# UCirKitUserStudy4-2.net
KiCad netlist of a schematic drawn in EAGLE
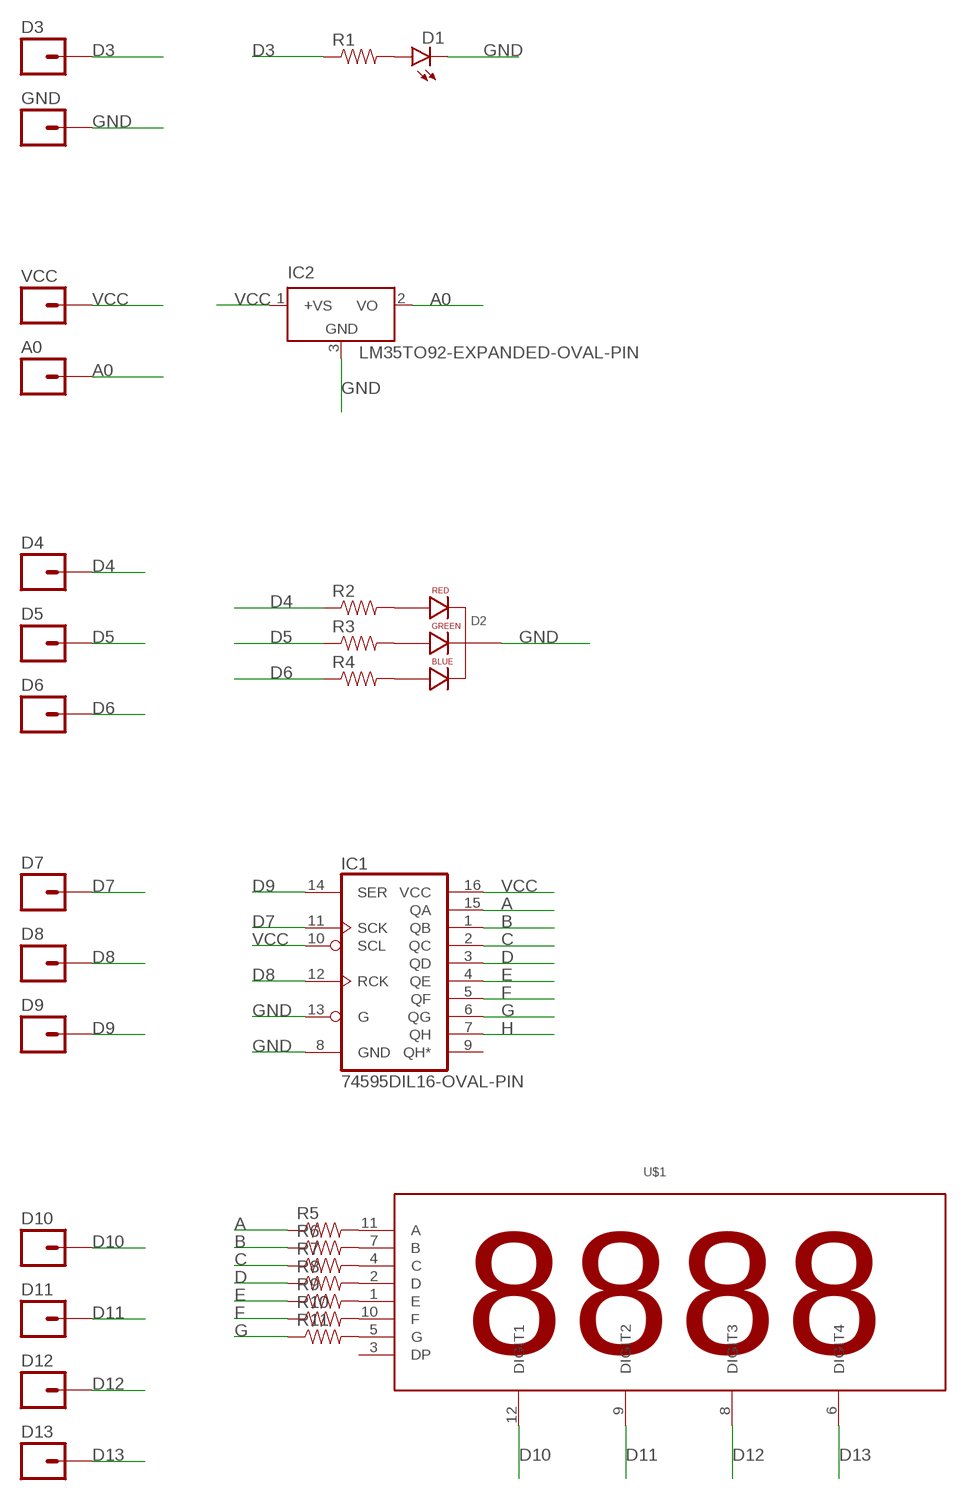
[diagram p0: schematic, sheet 1]

(export (version "E")
  (design (tool "Eeschema 10.0.6"))
  (components
    (comp (ref "A0")
      (value "M01OVAL_PIN")
      (footprint "eagle-import:1X01_OVAL_PIN")
      (libsource (lib "eagle-import") (part "M01OVAL_PIN"))
    )
    (comp (ref "D1")
      (value "LEDLED3MM-EXPANDED-OVAL-PIN")
      (footprint "eagle-import:LED3MM-EXPANDED-OVAL-PIN")
      (libsource (lib "eagle-import") (part "LEDLED3MM-EXPANDED-OVAL-PIN"))
    )
    (comp (ref "D2")
      (value "LED-RGB-CC-THRULED-RGB-THRU-EXPANDED-OVAL-PIN")
      (footprint "eagle-import:LED-RGB-THRU-EXPANDED-OVAL-PIN")
      (libsource (lib "eagle-import") (part "LED-RGB-CC-THRULED-RGB-THRU-EXPANDED-OVAL-PIN"))
    )
    (comp (ref "D3")
      (value "M01OVAL_PIN")
      (footprint "eagle-import:1X01_OVAL_PIN")
      (libsource (lib "eagle-import") (part "M01OVAL_PIN"))
    )
    (comp (ref "D4")
      (value "M01OVAL_PIN")
      (footprint "eagle-import:1X01_OVAL_PIN")
      (libsource (lib "eagle-import") (part "M01OVAL_PIN"))
    )
    (comp (ref "D5")
      (value "M01OVAL_PIN")
      (footprint "eagle-import:1X01_OVAL_PIN")
      (libsource (lib "eagle-import") (part "M01OVAL_PIN"))
    )
    (comp (ref "D6")
      (value "M01OVAL_PIN")
      (footprint "eagle-import:1X01_OVAL_PIN")
      (libsource (lib "eagle-import") (part "M01OVAL_PIN"))
    )
    (comp (ref "D7")
      (value "M01OVAL_PIN")
      (footprint "eagle-import:1X01_OVAL_PIN")
      (libsource (lib "eagle-import") (part "M01OVAL_PIN"))
    )
    (comp (ref "D8")
      (value "M01OVAL_PIN")
      (footprint "eagle-import:1X01_OVAL_PIN")
      (libsource (lib "eagle-import") (part "M01OVAL_PIN"))
    )
    (comp (ref "D9")
      (value "M01OVAL_PIN")
      (footprint "eagle-import:1X01_OVAL_PIN")
      (libsource (lib "eagle-import") (part "M01OVAL_PIN"))
    )
    (comp (ref "D10")
      (value "M01OVAL_PIN")
      (footprint "eagle-import:1X01_OVAL_PIN")
      (libsource (lib "eagle-import") (part "M01OVAL_PIN"))
    )
    (comp (ref "D11")
      (value "M01OVAL_PIN")
      (footprint "eagle-import:1X01_OVAL_PIN")
      (libsource (lib "eagle-import") (part "M01OVAL_PIN"))
    )
    (comp (ref "D12")
      (value "M01OVAL_PIN")
      (footprint "eagle-import:1X01_OVAL_PIN")
      (libsource (lib "eagle-import") (part "M01OVAL_PIN"))
    )
    (comp (ref "D13")
      (value "M01OVAL_PIN")
      (footprint "eagle-import:1X01_OVAL_PIN")
      (libsource (lib "eagle-import") (part "M01OVAL_PIN"))
    )
    (comp (ref "GND")
      (value "M01OVAL_PIN")
      (footprint "eagle-import:1X01_OVAL_PIN")
      (libsource (lib "eagle-import") (part "M01OVAL_PIN"))
    )
    (comp (ref "IC1")
      (value "74595DIL16-OVAL-PIN")
      (footprint "eagle-import:DIL16-OVAL-PIN")
      (libsource (lib "eagle-import") (part "74595DIL16-OVAL-PIN"))
    )
    (comp (ref "IC2")
      (value "LM35TO92-EXPANDED-OVAL-PIN")
      (footprint "eagle-import:TO92-EXPANDED-OVAL-PIN")
      (libsource (lib "eagle-import") (part "LM35TO92-EXPANDED-OVAL-PIN"))
    )
    (comp (ref "R1")
      (value "1KOHM-1/4W-1%(PTH)PTH-EXPANDED-OVAL-PIN")
      (footprint "eagle-import:PTH-EXPANDED-OVAL-PIN")
      (libsource (lib "eagle-import") (part "1KOHM-1/4W-1%(PTH)PTH-EXPANDED-OVAL-PIN"))
    )
    (comp (ref "R2")
      (value "1KOHM-1/4W-1%(PTH)PTH-EXPANDED-OVAL-PIN")
      (footprint "eagle-import:PTH-EXPANDED-OVAL-PIN")
      (libsource (lib "eagle-import") (part "1KOHM-1/4W-1%(PTH)PTH-EXPANDED-OVAL-PIN"))
    )
    (comp (ref "R3")
      (value "1KOHM-1/4W-1%(PTH)PTH-EXPANDED-OVAL-PIN")
      (footprint "eagle-import:PTH-EXPANDED-OVAL-PIN")
      (libsource (lib "eagle-import") (part "1KOHM-1/4W-1%(PTH)PTH-EXPANDED-OVAL-PIN"))
    )
    (comp (ref "R4")
      (value "1KOHM-1/4W-1%(PTH)PTH-EXPANDED-OVAL-PIN")
      (footprint "eagle-import:PTH-EXPANDED-OVAL-PIN")
      (libsource (lib "eagle-import") (part "1KOHM-1/4W-1%(PTH)PTH-EXPANDED-OVAL-PIN"))
    )
    (comp (ref "R5")
      (value "1KOHM-1/4W-1%(PTH)PTH-EXPANDED-OVAL-PIN")
      (footprint "eagle-import:PTH-EXPANDED-OVAL-PIN")
      (libsource (lib "eagle-import") (part "1KOHM-1/4W-1%(PTH)PTH-EXPANDED-OVAL-PIN"))
    )
    (comp (ref "R6")
      (value "1KOHM-1/4W-1%(PTH)PTH-EXPANDED-OVAL-PIN")
      (footprint "eagle-import:PTH-EXPANDED-OVAL-PIN")
      (libsource (lib "eagle-import") (part "1KOHM-1/4W-1%(PTH)PTH-EXPANDED-OVAL-PIN"))
    )
    (comp (ref "R7")
      (value "1KOHM-1/4W-1%(PTH)PTH-EXPANDED-OVAL-PIN")
      (footprint "eagle-import:PTH-EXPANDED-OVAL-PIN")
      (libsource (lib "eagle-import") (part "1KOHM-1/4W-1%(PTH)PTH-EXPANDED-OVAL-PIN"))
    )
    (comp (ref "R8")
      (value "1KOHM-1/4W-1%(PTH)PTH-EXPANDED-OVAL-PIN")
      (footprint "eagle-import:PTH-EXPANDED-OVAL-PIN")
      (libsource (lib "eagle-import") (part "1KOHM-1/4W-1%(PTH)PTH-EXPANDED-OVAL-PIN"))
    )
    (comp (ref "R9")
      (value "1KOHM-1/4W-1%(PTH)PTH-EXPANDED-OVAL-PIN")
      (footprint "eagle-import:PTH-EXPANDED-OVAL-PIN")
      (libsource (lib "eagle-import") (part "1KOHM-1/4W-1%(PTH)PTH-EXPANDED-OVAL-PIN"))
    )
    (comp (ref "R10")
      (value "1KOHM-1/4W-1%(PTH)PTH-EXPANDED-OVAL-PIN")
      (footprint "eagle-import:PTH-EXPANDED-OVAL-PIN")
      (libsource (lib "eagle-import") (part "1KOHM-1/4W-1%(PTH)PTH-EXPANDED-OVAL-PIN"))
    )
    (comp (ref "R11")
      (value "1KOHM-1/4W-1%(PTH)PTH-EXPANDED-OVAL-PIN")
      (footprint "eagle-import:PTH-EXPANDED-OVAL-PIN")
      (libsource (lib "eagle-import") (part "1KOHM-1/4W-1%(PTH)PTH-EXPANDED-OVAL-PIN"))
    )
    (comp (ref "U$1")
      (value "4DIGIT_SEVEN_SEGMENT4DIGIT_SEVEN_SEGMENT_OVAL_PIN")
      (footprint "eagle-import:4DIGIT_SEVEN_SEGMENT_OVAL_PIN")
      (libsource (lib "eagle-import") (part "4DIGIT_SEVEN_SEGMENT4DIGIT_SEVEN_SEGMENT_OVAL_PIN"))
    )
    (comp (ref "VCC")
      (value "M01OVAL_PIN")
      (footprint "eagle-import:1X01_OVAL_PIN")
      (libsource (lib "eagle-import") (part "M01OVAL_PIN"))
    )
  )
  (nets
    (net (code "1") (name "/A") (class "Default")
      (node (ref "IC1") (pin "15") (pinfunction "QA_15") (pintype "tri_state"))
      (node (ref "R5") (pin "P$1") (pinfunction "1_P$1") (pintype "passive"))
    )
    (net (code "2") (name "/A0") (class "Default")
      (node (ref "A0") (pin "1") (pinfunction "1_1") (pintype "passive"))
      (node (ref "IC2") (pin "2") (pinfunction "VO_2") (pintype "input"))
    )
    (net (code "3") (name "/B") (class "Default")
      (node (ref "IC1") (pin "1") (pinfunction "QB_1") (pintype "tri_state"))
      (node (ref "R6") (pin "P$1") (pinfunction "1_P$1") (pintype "passive"))
    )
    (net (code "4") (name "/C") (class "Default")
      (node (ref "IC1") (pin "2") (pinfunction "QC_2") (pintype "tri_state"))
      (node (ref "R7") (pin "P$1") (pinfunction "1_P$1") (pintype "passive"))
    )
    (net (code "5") (name "/D") (class "Default")
      (node (ref "IC1") (pin "3") (pinfunction "QD_3") (pintype "tri_state"))
      (node (ref "R8") (pin "P$1") (pinfunction "1_P$1") (pintype "passive"))
    )
    (net (code "6") (name "/D3") (class "Default")
      (node (ref "D3") (pin "1") (pinfunction "1_1") (pintype "passive"))
      (node (ref "R1") (pin "P$1") (pinfunction "1_P$1") (pintype "passive"))
    )
    (net (code "7") (name "/D4") (class "Default")
      (node (ref "D4") (pin "1") (pinfunction "1_1") (pintype "passive"))
      (node (ref "R2") (pin "P$1") (pinfunction "1_P$1") (pintype "passive"))
    )
    (net (code "8") (name "/D5") (class "Default")
      (node (ref "D5") (pin "1") (pinfunction "1_1") (pintype "passive"))
      (node (ref "R3") (pin "P$1") (pinfunction "1_P$1") (pintype "passive"))
    )
    (net (code "9") (name "/D6") (class "Default")
      (node (ref "D6") (pin "1") (pinfunction "1_1") (pintype "passive"))
      (node (ref "R4") (pin "P$1") (pinfunction "1_P$1") (pintype "passive"))
    )
    (net (code "10") (name "/D7") (class "Default")
      (node (ref "D7") (pin "1") (pinfunction "1_1") (pintype "passive"))
      (node (ref "IC1") (pin "11") (pinfunction "SCK_11") (pintype "input"))
    )
    (net (code "11") (name "/D8") (class "Default")
      (node (ref "D8") (pin "1") (pinfunction "1_1") (pintype "passive"))
      (node (ref "IC1") (pin "12") (pinfunction "RCK_12") (pintype "input"))
    )
    (net (code "12") (name "/D9") (class "Default")
      (node (ref "D9") (pin "1") (pinfunction "1_1") (pintype "passive"))
      (node (ref "IC1") (pin "14") (pinfunction "SER_14") (pintype "input"))
    )
    (net (code "13") (name "/D10") (class "Default")
      (node (ref "D10") (pin "1") (pinfunction "1_1") (pintype "passive"))
      (node (ref "U$1") (pin "12") (pinfunction "DIGIT1_12") (pintype "bidirectional"))
    )
    (net (code "14") (name "/D11") (class "Default")
      (node (ref "D11") (pin "1") (pinfunction "1_1") (pintype "passive"))
      (node (ref "U$1") (pin "9") (pinfunction "DIGIT2_9") (pintype "bidirectional"))
    )
    (net (code "15") (name "/D12") (class "Default")
      (node (ref "D12") (pin "1") (pinfunction "1_1") (pintype "passive"))
      (node (ref "U$1") (pin "8") (pinfunction "DIGIT3_8") (pintype "bidirectional"))
    )
    (net (code "16") (name "/D13") (class "Default")
      (node (ref "D13") (pin "1") (pinfunction "1_1") (pintype "passive"))
      (node (ref "U$1") (pin "6") (pinfunction "DIGIT4_6") (pintype "bidirectional"))
    )
    (net (code "17") (name "/E") (class "Default")
      (node (ref "IC1") (pin "4") (pinfunction "QE_4") (pintype "tri_state"))
      (node (ref "R9") (pin "P$1") (pinfunction "1_P$1") (pintype "passive"))
    )
    (net (code "18") (name "/F") (class "Default")
      (node (ref "IC1") (pin "5") (pinfunction "QF_5") (pintype "tri_state"))
      (node (ref "R10") (pin "P$1") (pinfunction "1_P$1") (pintype "passive"))
    )
    (net (code "19") (name "/G") (class "Default")
      (node (ref "IC1") (pin "6") (pinfunction "QG_6") (pintype "tri_state"))
      (node (ref "R11") (pin "P$1") (pinfunction "1_P$1") (pintype "passive"))
    )
    (net (code "20") (name "/GND") (class "Default")
      (node (ref "D1") (pin "K") (pinfunction "C_K") (pintype "passive"))
      (node (ref "D2") (pin "2") (pinfunction "CATHODE_2") (pintype "bidirectional"))
      (node (ref "GND") (pin "1") (pinfunction "1_1") (pintype "passive"))
      (node (ref "IC1") (pin "13") (pinfunction "G_13") (pintype "input"))
      (node (ref "IC1") (pin "8") (pinfunction "GND_8") (pintype "power_in"))
      (node (ref "IC2") (pin "3") (pinfunction "GND_3") (pintype "power_in"))
    )
    (net (code "21") (name "/H") (class "Default")
      (node (ref "IC1") (pin "7") (pinfunction "QH_7") (pintype "tri_state"))
    )
    (net (code "22") (name "/VCC") (class "Default")
      (node (ref "IC1") (pin "10") (pinfunction "SCL_10") (pintype "input"))
      (node (ref "IC1") (pin "16") (pinfunction "VCC_16") (pintype "power_in"))
      (node (ref "IC2") (pin "1") (pinfunction "+VS_1") (pintype "input"))
      (node (ref "VCC") (pin "1") (pinfunction "1_1") (pintype "passive"))
    )
    (net (code "23") (name "Net-(D2-BLUE_CATHODE)") (class "Default")
      (node (ref "D2") (pin "4") (pinfunction "BLUE_CATHODE_4") (pintype "bidirectional"))
      (node (ref "R4") (pin "P$2") (pinfunction "2_P$2") (pintype "passive"))
    )
    (net (code "24") (name "Net-(D2-GREEN_CATHODE)") (class "Default")
      (node (ref "D2") (pin "3") (pinfunction "GREEN_CATHODE_3") (pintype "bidirectional"))
      (node (ref "R3") (pin "P$2") (pinfunction "2_P$2") (pintype "passive"))
    )
    (net (code "25") (name "Net-(D2-RED_CATHODE)") (class "Default")
      (node (ref "D2") (pin "1") (pinfunction "RED_CATHODE_1") (pintype "bidirectional"))
      (node (ref "R2") (pin "P$2") (pinfunction "2_P$2") (pintype "passive"))
    )
    (net (code "26") (name "Net-(R1-2)") (class "Default")
      (node (ref "D1") (pin "A") (pinfunction "A_A") (pintype "passive"))
      (node (ref "R1") (pin "P$2") (pinfunction "2_P$2") (pintype "passive"))
    )
    (net (code "27") (name "Net-(R5-2)") (class "Default")
      (node (ref "R5") (pin "P$2") (pinfunction "2_P$2") (pintype "passive"))
      (node (ref "U$1") (pin "11") (pinfunction "A_11") (pintype "bidirectional"))
    )
    (net (code "28") (name "Net-(R6-2)") (class "Default")
      (node (ref "R6") (pin "P$2") (pinfunction "2_P$2") (pintype "passive"))
      (node (ref "U$1") (pin "7") (pinfunction "B_7") (pintype "bidirectional"))
    )
    (net (code "29") (name "Net-(R7-2)") (class "Default")
      (node (ref "R7") (pin "P$2") (pinfunction "2_P$2") (pintype "passive"))
      (node (ref "U$1") (pin "4") (pinfunction "C_4") (pintype "bidirectional"))
    )
    (net (code "30") (name "Net-(R8-2)") (class "Default")
      (node (ref "R8") (pin "P$2") (pinfunction "2_P$2") (pintype "passive"))
      (node (ref "U$1") (pin "2") (pinfunction "D_2") (pintype "bidirectional"))
    )
    (net (code "31") (name "Net-(R9-2)") (class "Default")
      (node (ref "R9") (pin "P$2") (pinfunction "2_P$2") (pintype "passive"))
      (node (ref "U$1") (pin "1") (pinfunction "E_1") (pintype "bidirectional"))
    )
    (net (code "32") (name "Net-(R10-2)") (class "Default")
      (node (ref "R10") (pin "P$2") (pinfunction "2_P$2") (pintype "passive"))
      (node (ref "U$1") (pin "10") (pinfunction "F_10") (pintype "bidirectional"))
    )
    (net (code "33") (name "Net-(R11-2)") (class "Default")
      (node (ref "R11") (pin "P$2") (pinfunction "2_P$2") (pintype "passive"))
      (node (ref "U$1") (pin "5") (pinfunction "G_5") (pintype "bidirectional"))
    )
    (net (code "34") (name "unconnected-(IC1-QH*-Pad9)") (class "Default")
      (node (ref "IC1") (pin "9") (pinfunction "QH*_9") (pintype "tri_state"))
    )
    (net (code "35") (name "unconnected-(U$1-DP-Pad3)") (class "Default")
      (node (ref "U$1") (pin "3") (pinfunction "DP_3") (pintype "bidirectional"))
    )
  )
)
